# CONTROL.net
KiCad netlist of a schematic drawn in Altium Designer
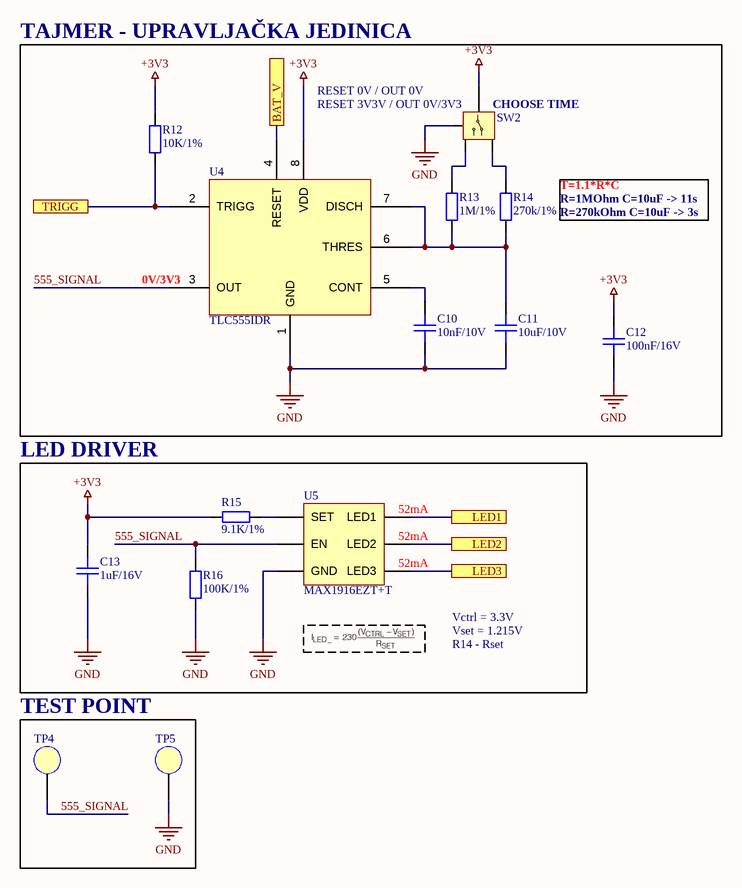
[diagram p0: CONTROL.SchDoc]

(export (version "E")
  (design (tool "Eeschema 10.0.6"))
  (components
    (comp (ref "C10")
      (value "10nF/10V")
      (footprint "CAP_0603")
      (description "10000 pF ±10% 50V Ceramic Capacitor X7R 0603 (1608 Metric)")
      (fields (field (name "MPN") "0603B103K500CT"))
      (libsource (lib "Library-AutomatskoOsvetljenje") (part "10nF/10V"))
    )
    (comp (ref "C11")
      (value "10uF/10V")
      (footprint "CAP_0603")
      (description "10 µF ±10% 10V Ceramic Capacitor X5R 0603 (1608 Metric)")
      (fields (field (name "MPN") "CL10A106KP8NNNC"))
      (libsource (lib "Library-AutomatskoOsvetljenje") (part "10uF/10V"))
    )
    (comp (ref "C12")
      (value "100nF/16V")
      (footprint "CAP_0603")
      (description "0.1 µF ±10% 16V Ceramic Capacitor X7R 0603 (1608 Metric)")
      (fields (field (name "MPN") "CC0603KRX7R7BB104"))
      (libsource (lib "Library-AutomatskoOsvetljenje") (part "100nF/16V"))
    )
    (comp (ref "C13")
      (value "1uF/16V")
      (footprint "CAP_0603")
      (description "1 µF ±5% 16V Ceramic Capacitor X7R 0603 (1608 Metric)")
      (fields (field (name "MPN") "0603YC105JAT2A"))
      (libsource (lib "Library-AutomatskoOsvetljenje") (part "1uF/16V"))
    )
    (comp (ref "R12")
      (value "10K/1%")
      (footprint "RES_0603")
      (description "10 kOhms ±1% 0.1W, 1/10W Chip Resistor 0603 (1608 Metric) Moisture Resistant Thick Film")
      (fields (field (name "MPN") "CR0603-FX-1002ELF"))
      (libsource (lib "Library-AutomatskoOsvetljenje") (part "10K/1%"))
    )
    (comp (ref "R13")
      (value "1M/1%")
      (footprint "RES_0603")
      (description "1 MOhms ±1% 0.1W, 1/10W Chip Resistor 0603 (1608 Metric) Automotive AEC-Q200 Thick Film")
      (fields (field (name "MPN") "RMCF0603FT1M00"))
      (libsource (lib "Library-AutomatskoOsvetljenje") (part "1M/1%"))
    )
    (comp (ref "R14")
      (value "270k/1%")
      (footprint "RES_0603")
      (description "270 kOhms ±1% 0.1W, 1/10W Chip Resistor 0603 (1608 Metric) Automotive AEC-Q200 Thick Film")
      (fields (field (name "MPN") "ERJ-3EKF2703V"))
      (libsource (lib "Library-AutomatskoOsvetljenje") (part "270k/1%"))
    )
    (comp (ref "R15")
      (value "9.1K/1%")
      (footprint "RES_0603")
      (description "9.1 kOhms ±1% 0.1W, 1/10W Chip Resistor 0603 (1608 Metric) Thick Film")
      (fields (field (name "MPN") "CRCW06039K10FKEAC"))
      (libsource (lib "Library-AutomatskoOsvetljenje") (part "9.1K/1%"))
    )
    (comp (ref "R16")
      (value "100K/1%")
      (footprint "RES_0603")
      (description "100 kOhms ±1% 0.1W, 1/10W Chip Resistor 0603 (1608 Metric) Automotive AEC-Q200 Thick Film")
      (fields (field (name "MPN") "ERJ-3EKF1003V"))
      (libsource (lib "Library-AutomatskoOsvetljenje") (part "100K/1%"))
    )
    (comp (ref "SW2")
      (value "SWITCH_MAIN")
      (footprint "SWITCH_SK-12F17-G_HORIZONTAL")
      (description "SWITCH SLIDE SPDT 300MA 30V")
      (fields (field (name "MPN") "SK-12F17-G 7"))
      (libsource (lib "Symbols") (part "SWITCH_MAIN"))
    )
    (comp (ref "TP4")
      (value "TESTPOINT")
      (footprint "TESTPOINT")
      (description "White PC Test Point, Miniature Phosphor Bronze Silver Plating Through Hole Mounting Type")
      (fields (field (name "MPN") "5002"))
      (libsource (lib "Library-AutomatskoOsvetljenje") (part "TESTPOINT"))
    )
    (comp (ref "TP5")
      (value "TESTPOINT")
      (footprint "TESTPOINT")
      (description "White PC Test Point, Miniature Phosphor Bronze Silver Plating Through Hole Mounting Type")
      (fields (field (name "MPN") "5002"))
      (libsource (lib "Library-AutomatskoOsvetljenje") (part "TESTPOINT"))
    )
    (comp (ref "U4")
      (value "TLC555IDR")
      (footprint "8-SOIC")
      (description "555 Type, Timer/Oscillator (Single) IC 2.1MHz 8-SOIC")
      (libsource (lib "Library-AutomatskoOsvetljenje") (part "TLC555IDR"))
    )
    (comp (ref "U5")
      (value "MAX1916EZT+T")
      (footprint "SOT23-6")
      (description "LED Driver IC 3 Output Linear Dimming 60mA TSOT-23-6")
      (libsource (lib "Library-AutomatskoOsvetljenje") (part "LED DRIVER MAX1916"))
    )
  )
  (nets
    (net (code "1") (name "+3V3") (class "Default")
      (node (ref "C12") (pin "2") (pinfunction "2_2") (pintype "passive"))
      (node (ref "C13") (pin "2") (pinfunction "2_2") (pintype "passive"))
      (node (ref "R12") (pin "2") (pinfunction "2_2") (pintype "passive"))
      (node (ref "R15") (pin "1") (pinfunction "1_1") (pintype "passive"))
      (node (ref "SW2") (pin "1") (pinfunction "1P_1") (pintype "passive"))
      (node (ref "U4") (pin "8") (pinfunction "VDD_8") (pintype "passive"))
    )
    (net (code "2") (name "/555_SIGNAL") (class "Default")
      (node (ref "R16") (pin "2") (pinfunction "2_2") (pintype "passive"))
      (node (ref "TP4") (pin "1") (pinfunction "TP_1") (pintype "passive"))
      (node (ref "U4") (pin "3") (pinfunction "OUT_3") (pintype "passive"))
      (node (ref "U5") (pin "1") (pinfunction "EN_1") (pintype "passive"))
    )
    (net (code "3") (name "/BAT_V") (class "Default")
      (node (ref "U4") (pin "4") (pinfunction "RESET_4") (pintype "passive"))
    )
    (net (code "4") (name "/LED1") (class "Default")
      (node (ref "U5") (pin "6") (pinfunction "LED1_6") (pintype "passive"))
    )
    (net (code "5") (name "/LED2") (class "Default")
      (node (ref "U5") (pin "5") (pinfunction "LED2_5") (pintype "passive"))
    )
    (net (code "6") (name "/LED3") (class "Default")
      (node (ref "U5") (pin "4") (pinfunction "LED3_4") (pintype "passive"))
    )
    (net (code "7") (name "/TRIGG") (class "Default")
      (node (ref "R12") (pin "1") (pinfunction "1_1") (pintype "passive"))
      (node (ref "U4") (pin "2") (pinfunction "TRIGG_2") (pintype "passive"))
    )
    (net (code "8") (name "GND") (class "Default")
      (node (ref "C10") (pin "1") (pinfunction "1_1") (pintype "passive"))
      (node (ref "C11") (pin "1") (pinfunction "1_1") (pintype "passive"))
      (node (ref "C12") (pin "1") (pinfunction "1_1") (pintype "passive"))
      (node (ref "C13") (pin "1") (pinfunction "1_1") (pintype "passive"))
      (node (ref "R16") (pin "1") (pinfunction "1_1") (pintype "passive"))
      (node (ref "SW2") (pin "4") (pinfunction "GND_4") (pintype "passive"))
      (node (ref "TP5") (pin "1") (pinfunction "TP_1") (pintype "passive"))
      (node (ref "U4") (pin "1") (pinfunction "GND_1") (pintype "passive"))
      (node (ref "U5") (pin "2") (pinfunction "GND_2") (pintype "passive"))
    )
    (net (code "9") (name "Net-(SW2-2T)") (class "Default")
      (node (ref "R13") (pin "2") (pinfunction "2_2") (pintype "passive"))
      (node (ref "SW2") (pin "2") (pinfunction "2T_2") (pintype "passive"))
    )
    (net (code "10") (name "Net-(SW2-3T)") (class "Default")
      (node (ref "R14") (pin "2") (pinfunction "2_2") (pintype "passive"))
      (node (ref "SW2") (pin "3") (pinfunction "3T_3") (pintype "passive"))
    )
    (net (code "11") (name "Net-(U4-CONT)") (class "Default")
      (node (ref "C10") (pin "2") (pinfunction "2_2") (pintype "passive"))
      (node (ref "U4") (pin "5") (pinfunction "CONT_5") (pintype "passive"))
    )
    (net (code "12") (name "Net-(U4-DISCH)") (class "Default")
      (node (ref "C11") (pin "2") (pinfunction "2_2") (pintype "passive"))
      (node (ref "R13") (pin "1") (pinfunction "1_1") (pintype "passive"))
      (node (ref "R14") (pin "1") (pinfunction "1_1") (pintype "passive"))
      (node (ref "U4") (pin "6") (pinfunction "THRES_6") (pintype "passive"))
      (node (ref "U4") (pin "7") (pinfunction "DISCH_7") (pintype "passive"))
    )
    (net (code "13") (name "Net-(U5-SET)") (class "Default")
      (node (ref "R15") (pin "2") (pinfunction "2_2") (pintype "passive"))
      (node (ref "U5") (pin "3") (pinfunction "SET_3") (pintype "passive"))
    )
  )
)
